# STM32F103C8.net
KiCad netlist of a schematic drawn in Altium Designer
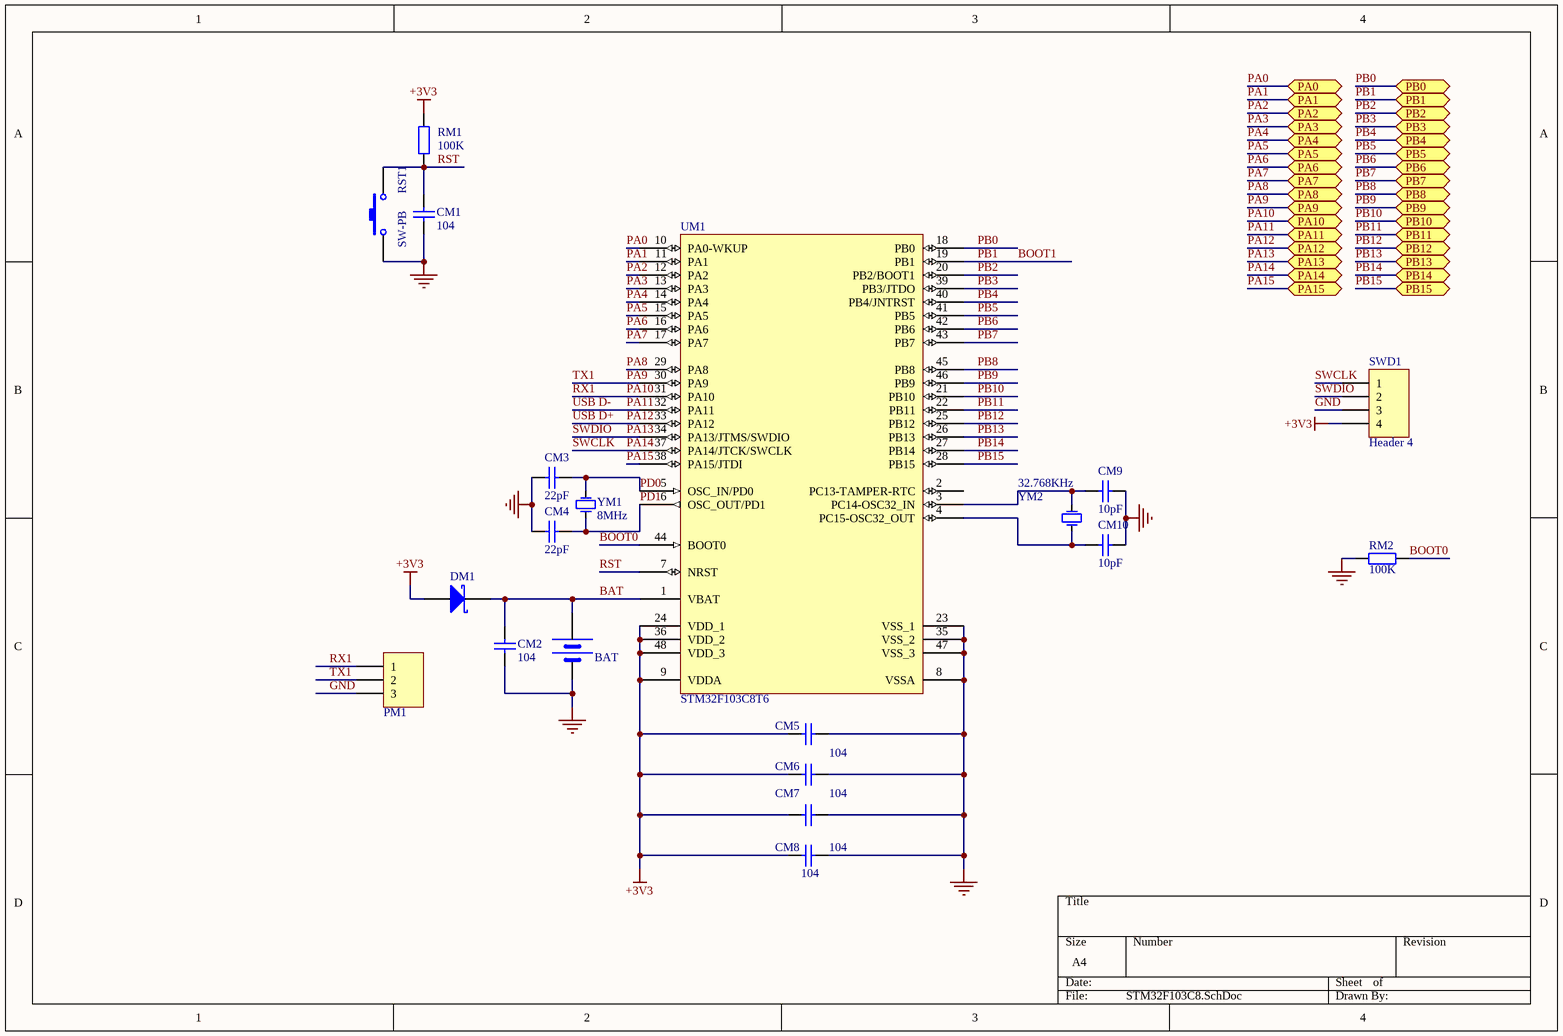
[diagram p0: STM32F103C8.SchDoc]

(export (version "E")
  (design (tool "Eeschema 10.0.6"))
  (components
    (comp (ref "BAT") (value "BATT") (footprint "BATM") (libsource (lib "Peace的集成库") (part "BAT")))
    (comp (ref "CM1")
      (value "104")
      (footprint "CAPC1608N")
      (description "Capacitor")
      (fields (field (name "Comment") "Cap1") (field (name "PUBLISHER") "Altium Limited"))
      (libsource (lib "Peace的集成库") (part "Cap1"))
    )
    (comp (ref "CM2")
      (value "104")
      (footprint "CAPC1608N")
      (description "Capacitor")
      (fields (field (name "Comment") "Cap1") (field (name "PUBLISHER") "Altium Limited"))
      (libsource (lib "Peace的集成库") (part "Cap1"))
    )
    (comp (ref "CM3")
      (value "22pF")
      (footprint "CAPC1608N")
      (description "Capacitor")
      (fields (field (name "Comment") "Cap1") (field (name "PUBLISHER") "Altium Limited"))
      (libsource (lib "Peace的集成库") (part "Cap1"))
    )
    (comp (ref "CM4")
      (value "22pF")
      (footprint "CAPC1608N")
      (description "Capacitor")
      (fields (field (name "Comment") "Cap1") (field (name "PUBLISHER") "Altium Limited"))
      (libsource (lib "Peace的集成库") (part "Cap1"))
    )
    (comp (ref "CM5")
      (value "104")
      (footprint "CAPC1608N")
      (description "Capacitor")
      (fields (field (name "Comment") "Cap1") (field (name "PUBLISHER") "Altium Limited"))
      (libsource (lib "Peace的集成库") (part "Cap1"))
    )
    (comp (ref "CM6")
      (value "104")
      (footprint "CAPC1608N")
      (description "Capacitor")
      (fields (field (name "Comment") "Cap1") (field (name "PUBLISHER") "Altium Limited"))
      (libsource (lib "Peace的集成库") (part "Cap1"))
    )
    (comp (ref "CM7")
      (value "104")
      (footprint "CAPC1608N")
      (description "Capacitor")
      (fields (field (name "Comment") "Cap1") (field (name "PUBLISHER") "Altium Limited"))
      (libsource (lib "Peace的集成库") (part "Cap1"))
    )
    (comp (ref "CM8")
      (value "104")
      (footprint "CAPC1608N")
      (description "Capacitor")
      (fields (field (name "Comment") "Cap1") (field (name "PUBLISHER") "Altium Limited"))
      (libsource (lib "Peace的集成库") (part "Cap1"))
    )
    (comp (ref "CM9")
      (value "10pF")
      (footprint "CAPC1608N")
      (description "Capacitor")
      (fields (field (name "Comment") "Cap1") (field (name "PUBLISHER") "Altium Limited"))
      (libsource (lib "Peace的集成库") (part "Cap1"))
    )
    (comp (ref "CM10")
      (value "10pF")
      (footprint "CAPC1608N")
      (description "Capacitor")
      (fields (field (name "Comment") "Cap1") (field (name "PUBLISHER") "Altium Limited"))
      (libsource (lib "Peace的集成库") (part "Cap1"))
    )
    (comp (ref "DM1")
      (value "D Schottky")
      (footprint "DO-214AC")
      (description "Schottky Diode")
      (fields (field (name "PUBLISHER") "Altium Limited"))
      (libsource (lib "Peace的集成库") (part "D Schottky"))
    )
    (comp (ref "PM1")
      (value "Header 3")
      (footprint "HDR1X3")
      (description "Header, 3-Pin")
      (fields (field (name "PUBLISHER") "Altium Limited"))
      (libsource (lib "Peace的集成库") (part "Header 3"))
    )
    (comp (ref "RM1")
      (value "100K")
      (footprint "RESC1608N")
      (description "Resistor")
      (fields (field (name "Comment") "Res1") (field (name "PUBLISHER") "Altium Limited"))
      (libsource (lib "") (part "Res1_1"))
    )
    (comp (ref "RM2")
      (value "100K")
      (footprint "RESC1608N")
      (description "Resistor")
      (fields (field (name "Comment") "Res1") (field (name "PUBLISHER") "Altium Limited"))
      (libsource (lib "Peace的集成库") (part "Res1"))
    )
    (comp (ref "RST1")
      (value "SW-PB")
      (footprint "SW-3x6")
      (description "Switch")
      (fields (field (name "PUBLISHER") "Altium Limited"))
      (libsource (lib "Peace的集成库") (part "SW-PB"))
    )
    (comp (ref "SWD1")
      (value "Header 4")
      (footprint "HDR1X4")
      (description "Header, 4-Pin")
      (fields (field (name "PUBLISHER") "Altium Limited"))
      (libsource (lib "Miscellaneous Connectors") (part "Header 4"))
    )
    (comp (ref "UM1")
      (value "STM32F103C8T6")
      (footprint "LQFP48_L")
      (description "STM32 ARM-based 32-bit MCU with 64 Kbytes Flash, 48-pin LQFP, Industrial Temperature")
      (fields (field (name "PUBLISHER") "Altium Limited"))
      (libsource (lib "Peace的集成库") (part "STM32F103C8T6"))
    )
    (comp (ref "YM1")
      (value "8MHz")
      (footprint "XTAL-5032")
      (description "Crystal Oscillator")
      (fields (field (name "PUBLISHER") "Altium Limited"))
      (libsource (lib "原理图库") (part "XTAL"))
    )
    (comp (ref "YM2")
      (value "32.768KHz")
      (footprint "XTAL-206 - duplicate")
      (description "Crystal Oscillator")
      (fields (field (name "PUBLISHER") "Altium Limited"))
      (libsource (lib "原理图库") (part "XTAL"))
    )
  )
  (nets
    (net (code "1") (name "+3V3") (class "Default")
      (node (ref "CM5") (pin "2") (pinfunction "2_2") (pintype "passive"))
      (node (ref "CM6") (pin "2") (pinfunction "2_2") (pintype "passive"))
      (node (ref "CM7") (pin "2") (pinfunction "2_2") (pintype "passive"))
      (node (ref "CM8") (pin "2") (pinfunction "2_2") (pintype "passive"))
      (node (ref "DM1") (pin "1") (pinfunction "A_1") (pintype "passive"))
      (node (ref "RM1") (pin "2") (pinfunction "2_2") (pintype "passive"))
      (node (ref "SWD1") (pin "4") (pinfunction "4_4") (pintype "passive"))
      (node (ref "UM1") (pin "24") (pinfunction "VDD_1_24") (pintype "power_in"))
      (node (ref "UM1") (pin "36") (pinfunction "VDD_2_36") (pintype "power_in"))
      (node (ref "UM1") (pin "48") (pinfunction "VDD_3_48") (pintype "power_in"))
      (node (ref "UM1") (pin "9") (pinfunction "VDDA_9") (pintype "power_in"))
    )
    (net (code "2") (name "/BAT") (class "Default")
      (node (ref "BAT") (pin "1") (pinfunction "VCC_1") (pintype "passive"))
      (node (ref "CM2") (pin "2") (pinfunction "2_2") (pintype "passive"))
      (node (ref "DM1") (pin "2") (pinfunction "K_2") (pintype "passive"))
      (node (ref "UM1") (pin "1") (pinfunction "VBAT_1") (pintype "power_in"))
    )
    (net (code "3") (name "/BOOT0") (class "Default")
      (node (ref "RM2") (pin "1") (pinfunction "1_1") (pintype "passive"))
      (node (ref "UM1") (pin "44") (pinfunction "BOOT0_44") (pintype "input"))
    )
    (net (code "4") (name "/BOOT1") (class "Default")
      (node (ref "UM1") (pin "19") (pinfunction "PB1_19") (pintype "bidirectional"))
    )
    (net (code "5") (name "/PA0") (class "Default")
      (node (ref "UM1") (pin "10") (pinfunction "PA0-WKUP_10") (pintype "bidirectional"))
    )
    (net (code "6") (name "/PA1") (class "Default")
      (node (ref "UM1") (pin "11") (pinfunction "PA1_11") (pintype "bidirectional"))
    )
    (net (code "7") (name "/PA2") (class "Default")
      (node (ref "UM1") (pin "12") (pinfunction "PA2_12") (pintype "bidirectional"))
    )
    (net (code "8") (name "/PA3") (class "Default")
      (node (ref "UM1") (pin "13") (pinfunction "PA3_13") (pintype "bidirectional"))
    )
    (net (code "9") (name "/PA4") (class "Default")
      (node (ref "UM1") (pin "14") (pinfunction "PA4_14") (pintype "bidirectional"))
    )
    (net (code "10") (name "/PA5") (class "Default")
      (node (ref "UM1") (pin "15") (pinfunction "PA5_15") (pintype "bidirectional"))
    )
    (net (code "11") (name "/PA6") (class "Default")
      (node (ref "UM1") (pin "16") (pinfunction "PA6_16") (pintype "bidirectional"))
    )
    (net (code "12") (name "/PA7") (class "Default")
      (node (ref "UM1") (pin "17") (pinfunction "PA7_17") (pintype "bidirectional"))
    )
    (net (code "13") (name "/PA8") (class "Default")
      (node (ref "UM1") (pin "29") (pinfunction "PA8_29") (pintype "bidirectional"))
    )
    (net (code "14") (name "/PA9") (class "Default")
      (node (ref "PM1") (pin "2") (pinfunction "2_2") (pintype "passive"))
      (node (ref "UM1") (pin "30") (pinfunction "PA9_30") (pintype "bidirectional"))
    )
    (net (code "15") (name "/PA10") (class "Default")
      (node (ref "PM1") (pin "1") (pinfunction "1_1") (pintype "passive"))
      (node (ref "UM1") (pin "31") (pinfunction "PA10_31") (pintype "bidirectional"))
    )
    (net (code "16") (name "/PA11") (class "Default")
      (node (ref "UM1") (pin "32") (pinfunction "PA11_32") (pintype "bidirectional"))
    )
    (net (code "17") (name "/PA12") (class "Default")
      (node (ref "UM1") (pin "33") (pinfunction "PA12_33") (pintype "bidirectional"))
    )
    (net (code "18") (name "/PA13") (class "Default")
      (node (ref "SWD1") (pin "2") (pinfunction "2_2") (pintype "passive"))
      (node (ref "UM1") (pin "34") (pinfunction "PA13/JTMS/SWDIO_34") (pintype "bidirectional"))
    )
    (net (code "19") (name "/PA14") (class "Default")
      (node (ref "SWD1") (pin "1") (pinfunction "1_1") (pintype "passive"))
      (node (ref "UM1") (pin "37") (pinfunction "PA14/JTCK/SWCLK_37") (pintype "bidirectional"))
    )
    (net (code "20") (name "/PA15") (class "Default")
      (node (ref "UM1") (pin "38") (pinfunction "PA15/JTDI_38") (pintype "bidirectional"))
    )
    (net (code "21") (name "/PB0") (class "Default")
      (node (ref "UM1") (pin "18") (pinfunction "PB0_18") (pintype "bidirectional"))
    )
    (net (code "22") (name "/PB2") (class "Default")
      (node (ref "UM1") (pin "20") (pinfunction "PB2/BOOT1_20") (pintype "bidirectional"))
    )
    (net (code "23") (name "/PB3") (class "Default")
      (node (ref "UM1") (pin "39") (pinfunction "PB3/JTDO_39") (pintype "bidirectional"))
    )
    (net (code "24") (name "/PB4") (class "Default")
      (node (ref "UM1") (pin "40") (pinfunction "PB4/JNTRST_40") (pintype "bidirectional"))
    )
    (net (code "25") (name "/PB5") (class "Default")
      (node (ref "UM1") (pin "41") (pinfunction "PB5_41") (pintype "bidirectional"))
    )
    (net (code "26") (name "/PB6") (class "Default")
      (node (ref "UM1") (pin "42") (pinfunction "PB6_42") (pintype "bidirectional"))
    )
    (net (code "27") (name "/PB7") (class "Default")
      (node (ref "UM1") (pin "43") (pinfunction "PB7_43") (pintype "bidirectional"))
    )
    (net (code "28") (name "/PB8") (class "Default")
      (node (ref "UM1") (pin "45") (pinfunction "PB8_45") (pintype "bidirectional"))
    )
    (net (code "29") (name "/PB9") (class "Default")
      (node (ref "UM1") (pin "46") (pinfunction "PB9_46") (pintype "bidirectional"))
    )
    (net (code "30") (name "/PB10") (class "Default")
      (node (ref "UM1") (pin "21") (pinfunction "PB10_21") (pintype "bidirectional"))
    )
    (net (code "31") (name "/PB11") (class "Default")
      (node (ref "UM1") (pin "22") (pinfunction "PB11_22") (pintype "bidirectional"))
    )
    (net (code "32") (name "/PB12") (class "Default")
      (node (ref "UM1") (pin "25") (pinfunction "PB12_25") (pintype "bidirectional"))
    )
    (net (code "33") (name "/PB13") (class "Default")
      (node (ref "UM1") (pin "26") (pinfunction "PB13_26") (pintype "bidirectional"))
    )
    (net (code "34") (name "/PB14") (class "Default")
      (node (ref "UM1") (pin "27") (pinfunction "PB14_27") (pintype "bidirectional"))
    )
    (net (code "35") (name "/PB15") (class "Default")
      (node (ref "UM1") (pin "28") (pinfunction "PB15_28") (pintype "bidirectional"))
    )
    (net (code "36") (name "/PD0") (class "Default")
      (node (ref "CM3") (pin "2") (pinfunction "2_2") (pintype "passive"))
      (node (ref "UM1") (pin "5") (pinfunction "OSC_IN/PD0_5") (pintype "input"))
      (node (ref "YM1") (pin "2") (pinfunction "OSC2_2") (pintype "passive"))
    )
    (net (code "37") (name "/PD1") (class "Default")
      (node (ref "CM4") (pin "2") (pinfunction "2_2") (pintype "passive"))
      (node (ref "UM1") (pin "6") (pinfunction "OSC_OUT/PD1_6") (pintype "output"))
      (node (ref "YM1") (pin "1") (pinfunction "OSC1_1") (pintype "passive"))
    )
    (net (code "38") (name "/RST") (class "Default")
      (node (ref "CM1") (pin "2") (pinfunction "2_2") (pintype "passive"))
      (node (ref "RM1") (pin "1") (pinfunction "1_1") (pintype "passive"))
      (node (ref "RST1") (pin "2") (pinfunction "2_2") (pintype "passive"))
      (node (ref "UM1") (pin "7") (pinfunction "NRST_7") (pintype "bidirectional"))
    )
    (net (code "39") (name "GND") (class "Default")
      (node (ref "BAT") (pin "2") (pinfunction "GND_2") (pintype "passive"))
      (node (ref "CM1") (pin "1") (pinfunction "1_1") (pintype "passive"))
      (node (ref "CM10") (pin "1") (pinfunction "1_1") (pintype "passive"))
      (node (ref "CM2") (pin "1") (pinfunction "1_1") (pintype "passive"))
      (node (ref "CM3") (pin "1") (pinfunction "1_1") (pintype "passive"))
      (node (ref "CM4") (pin "1") (pinfunction "1_1") (pintype "passive"))
      (node (ref "CM5") (pin "1") (pinfunction "1_1") (pintype "passive"))
      (node (ref "CM6") (pin "1") (pinfunction "1_1") (pintype "passive"))
      (node (ref "CM7") (pin "1") (pinfunction "1_1") (pintype "passive"))
      (node (ref "CM8") (pin "1") (pinfunction "1_1") (pintype "passive"))
      (node (ref "CM9") (pin "1") (pinfunction "1_1") (pintype "passive"))
      (node (ref "PM1") (pin "3") (pinfunction "3_3") (pintype "passive"))
      (node (ref "RM2") (pin "2") (pinfunction "2_2") (pintype "passive"))
      (node (ref "RST1") (pin "1") (pinfunction "1_1") (pintype "passive"))
      (node (ref "SWD1") (pin "3") (pinfunction "3_3") (pintype "passive"))
      (node (ref "UM1") (pin "23") (pinfunction "VSS_1_23") (pintype "power_in"))
      (node (ref "UM1") (pin "35") (pinfunction "VSS_2_35") (pintype "power_in"))
      (node (ref "UM1") (pin "47") (pinfunction "VSS_3_47") (pintype "power_in"))
      (node (ref "UM1") (pin "8") (pinfunction "VSSA_8") (pintype "power_in"))
    )
    (net (code "40") (name "Net-(UM1-PC14-OSC32_IN)") (class "Default")
      (node (ref "CM9") (pin "2") (pinfunction "2_2") (pintype "passive"))
      (node (ref "UM1") (pin "3") (pinfunction "PC14-OSC32_IN_3") (pintype "bidirectional"))
      (node (ref "YM2") (pin "1") (pinfunction "OSC1_1") (pintype "passive"))
    )
    (net (code "41") (name "Net-(UM1-PC15-OSC32_OUT)") (class "Default")
      (node (ref "CM10") (pin "2") (pinfunction "2_2") (pintype "passive"))
      (node (ref "UM1") (pin "4") (pinfunction "PC15-OSC32_OUT_4") (pintype "bidirectional"))
      (node (ref "YM2") (pin "2") (pinfunction "OSC2_2") (pintype "passive"))
    )
    (net (code "42") (name "unconnected-(UM1-PC13-TAMPER-RTC-Pad2)") (class "Default")
      (node (ref "UM1") (pin "2") (pinfunction "PC13-TAMPER-RTC_2") (pintype "bidirectional"))
    )
  )
)
